# MainBoard_V1p0_PSU.net
KiCad netlist of a schematic drawn in Altium Designer
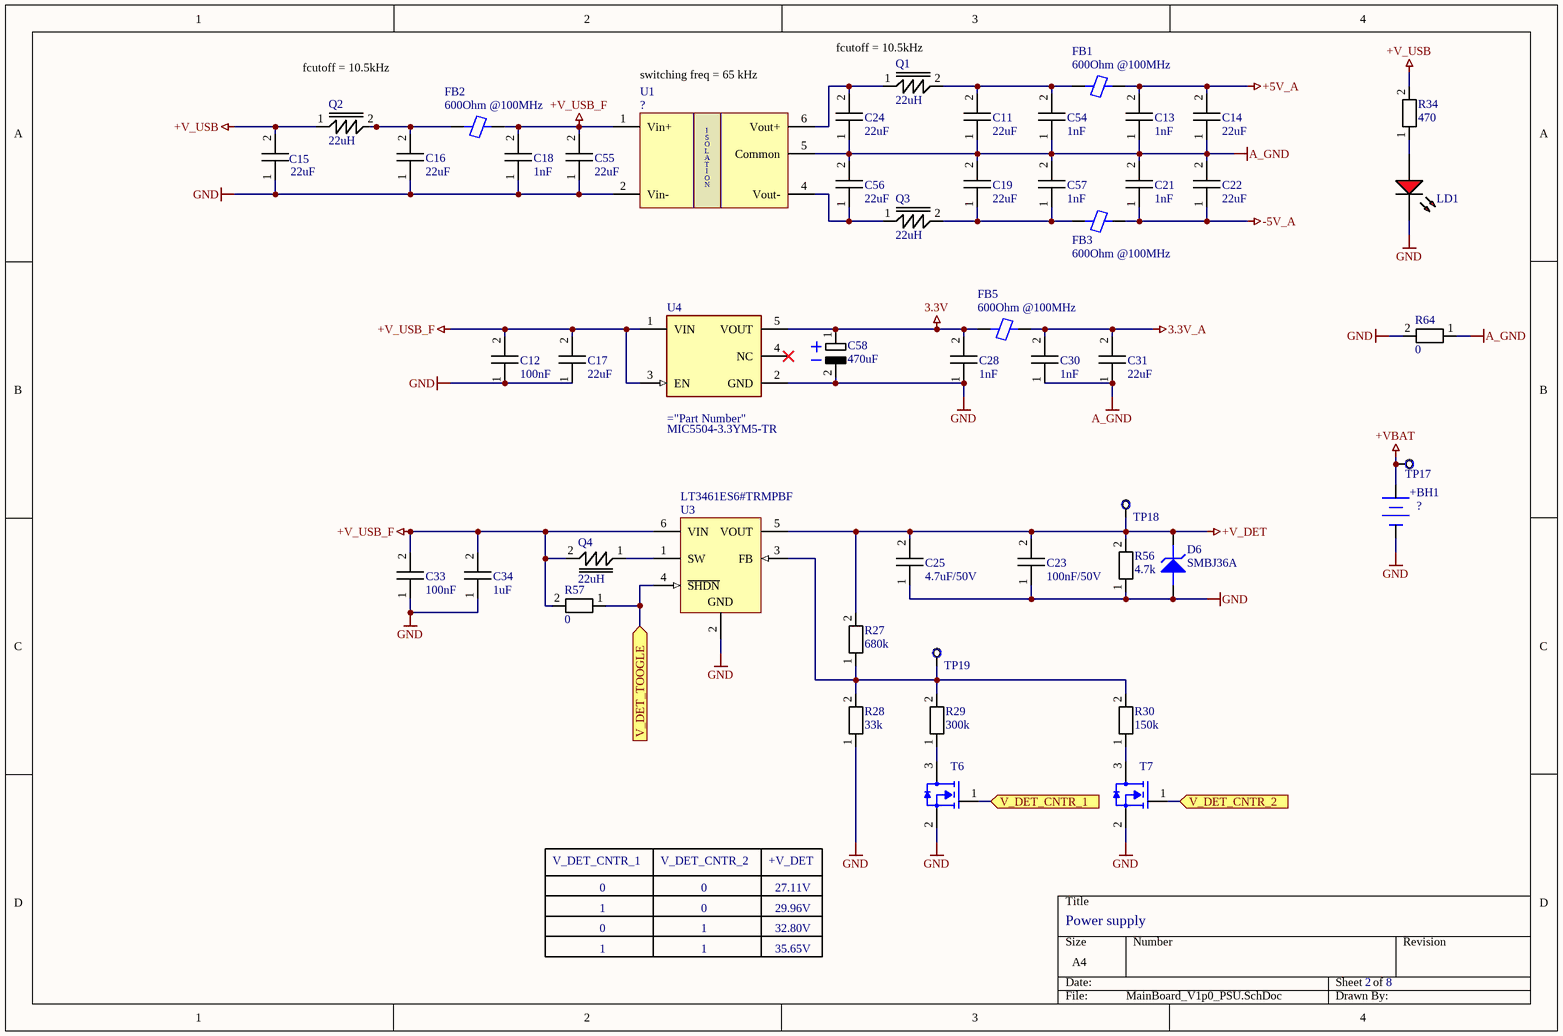
[diagram p0: MainBoard_V1p0_PSU.SchDoc]

(export (version "E")
  (design (tool "Eeschema 10.0.6"))
  (components
    (comp (ref "BH1")
      (value "?")
      (footprint "BATTERY_HOLDER_KEYSTONE_3002")
      (description "KEYSTONE 3002 (CR2032)")
      (libsource (lib "Schlib1") (part "BATTERY_HOLDER"))
    )
    (comp (ref "C11") (value "22uF") (footprint "1210_C") (libsource (lib "Schlib1") (part "CAPACITOR")))
    (comp (ref "C12") (value "100nF") (footprint "0805_C") (libsource (lib "Schlib1") (part "CAPACITOR")))
    (comp (ref "C13") (value "1nF") (footprint "0805_C") (libsource (lib "Schlib1") (part "CAPACITOR")))
    (comp (ref "C14") (value "22uF") (footprint "1210_C") (libsource (lib "Schlib1") (part "CAPACITOR")))
    (comp (ref "C15") (value "22uF") (footprint "1210_C") (libsource (lib "Schlib1") (part "CAPACITOR")))
    (comp (ref "C16") (value "22uF") (footprint "0805_C") (libsource (lib "Schlib1") (part "CAPACITOR")))
    (comp (ref "C17") (value "22uF") (footprint "1210_C") (libsource (lib "Schlib1") (part "CAPACITOR")))
    (comp (ref "C18") (value "1nF") (footprint "0805_C") (libsource (lib "Schlib1") (part "CAPACITOR")))
    (comp (ref "C19") (value "22uF") (footprint "1210_C") (libsource (lib "Schlib1") (part "CAPACITOR")))
    (comp (ref "C21") (value "1nF") (footprint "0805_C") (libsource (lib "Schlib1") (part "CAPACITOR")))
    (comp (ref "C22") (value "22uF") (footprint "1210_C") (libsource (lib "Schlib1") (part "CAPACITOR")))
    (comp (ref "C23") (value "100nF/50V") (footprint "0805_C") (libsource (lib "Schlib1") (part "CAPACITOR")))
    (comp (ref "C24") (value "22uF") (footprint "1210_C") (libsource (lib "Schlib1") (part "CAPACITOR")))
    (comp (ref "C25") (value "4.7uF/50V") (footprint "0805_C") (libsource (lib "Schlib1") (part "CAPACITOR")))
    (comp (ref "C28") (value "1nF") (footprint "0805_C") (libsource (lib "Schlib1") (part "CAPACITOR")))
    (comp (ref "C30") (value "1nF") (footprint "0805_C") (libsource (lib "Schlib1") (part "CAPACITOR")))
    (comp (ref "C31") (value "22uF") (footprint "1210_C") (libsource (lib "Schlib1") (part "CAPACITOR")))
    (comp (ref "C33") (value "100nF") (footprint "0805_C") (libsource (lib "Schlib1") (part "CAPACITOR")))
    (comp (ref "C34") (value "1uF") (footprint "0805_C") (libsource (lib "Schlib1") (part "CAPACITOR")))
    (comp (ref "C54") (value "1nF") (footprint "0805_C") (libsource (lib "Schlib1") (part "CAPACITOR")))
    (comp (ref "C55") (value "22uF") (footprint "1210_C") (libsource (lib "Schlib1") (part "CAPACITOR")))
    (comp (ref "C56") (value "22uF") (footprint "1210_C") (libsource (lib "Schlib1") (part "CAPACITOR")))
    (comp (ref "C57") (value "1nF") (footprint "0805_C") (libsource (lib "Schlib1") (part "CAPACITOR")))
    (comp (ref "C58")
      (value "470uF")
      (footprint "CAPAE9383X110M")
      (libsource (lib "Schlib1") (part "CAPACITOR_ELCO"))
    )
    (comp (ref "D6")
      (value "SMBJ36A")
      (footprint "DO-214AA (SMB)")
      (libsource (lib "Schlib1") (part "DIODE_TVS"))
    )
    (comp (ref "FB1")
      (value "600Ohm @100MHz")
      (footprint "0805_FB")
      (libsource (lib "Schlib1") (part "FERRITE_BEAD"))
    )
    (comp (ref "FB2")
      (value "600Ohm @100MHz")
      (footprint "0805_FB")
      (libsource (lib "Schlib1") (part "FERRITE_BEAD"))
    )
    (comp (ref "FB3")
      (value "600Ohm @100MHz")
      (footprint "0805_FB")
      (libsource (lib "Schlib1") (part "FERRITE_BEAD"))
    )
    (comp (ref "FB5")
      (value "600Ohm @100MHz")
      (footprint "0805_FB")
      (libsource (lib "Schlib1") (part "FERRITE_BEAD"))
    )
    (comp (ref "LD1")
      (value "LED_RED")
      (footprint "LED_SMD_90DEG_RED")
      (libsource (lib "Schlib1") (part "LED_RED"))
    )
    (comp (ref "Q1") (value "22uH") (footprint "1210") (libsource (lib "Schlib1") (part "COIL")))
    (comp (ref "Q2") (value "22uH") (footprint "1210") (libsource (lib "Schlib1") (part "COIL")))
    (comp (ref "Q3") (value "22uH") (footprint "1210") (libsource (lib "Schlib1") (part "COIL")))
    (comp (ref "Q4") (value "22uH") (footprint "1210") (libsource (lib "Schlib1") (part "COIL")))
    (comp (ref "R27") (value "680k") (footprint "0805") (libsource (lib "Schlib1") (part "RESISTOR")))
    (comp (ref "R28") (value "33k") (footprint "0805") (libsource (lib "Schlib1") (part "RESISTOR")))
    (comp (ref "R29") (value "300k") (footprint "0805") (libsource (lib "Schlib1") (part "RESISTOR")))
    (comp (ref "R30") (value "150k") (footprint "0805") (libsource (lib "Schlib1") (part "RESISTOR")))
    (comp (ref "R34") (value "470") (footprint "0805") (libsource (lib "Schlib1") (part "RESISTOR")))
    (comp (ref "R56") (value "4.7k") (footprint "0805") (libsource (lib "Schlib1") (part "RESISTOR")))
    (comp (ref "R57") (value "0") (footprint "0805") (libsource (lib "Schlib1") (part "RESISTOR")))
    (comp (ref "R64") (value "0") (footprint "0805") (libsource (lib "Schlib1") (part "RESISTOR")))
    (comp (ref "T6")
      (value "MMBF170")
      (footprint "SOT23")
      (description "N MOSFET")
      (libsource (lib "Schlib1") (part "MMBF170"))
    )
    (comp (ref "T7")
      (value "MMBF170")
      (footprint "SOT23")
      (description "N MOSFET")
      (libsource (lib "Schlib1") (part "MMBF170"))
    )
    (comp (ref "TP17") (value "?") (footprint "PAD_40") (libsource (lib "Schlib1") (part "TESTPOINT")))
    (comp (ref "TP18") (value "?") (footprint "PAD_40") (libsource (lib "Schlib1") (part "TESTPOINT")))
    (comp (ref "TP19") (value "?") (footprint "PAD_40") (libsource (lib "Schlib1") (part "TESTPOINT")))
    (comp (ref "U1")
      (value "?")
      (footprint "SIP_6")
      (description "MEA1D0505SC Isolated DC/DC Converters +/-5V 100mA")
      (libsource (lib "pwr_mgt") (part "NKA0505SC"))
    )
    (comp (ref "U3")
      (value "LT3461ES6#TRMPBF")
      (footprint "LT-S6-6-TSOT-23_L")
      (libsource (lib "pwr_mgt") (part "LT3461"))
    )
    (comp (ref "U4")
      (value "MIC5504-3.3YM5-TR")
      (footprint "SOT23-5")
      (libsource (lib "pwr_mgt") (part "MIC5504-3.3YM5-TR"))
    )
  )
  (nets
    (net (code "1") (name "+5V_A") (class "Default")
      (node (ref "C13") (pin "2") (pinfunction "2_2") (pintype "passive"))
      (node (ref "C14") (pin "2") (pinfunction "2_2") (pintype "passive"))
      (node (ref "FB1") (pin "2") (pinfunction "2_2") (pintype "passive"))
    )
    (net (code "2") (name "+VBAT") (class "Default")
      (node (ref "BH1") (pin "1") (pinfunction "1_1") (pintype "passive"))
      (node (ref "TP17") (pin "1") (pinfunction "1_1") (pintype "passive"))
    )
    (net (code "3") (name "+V_DET") (class "Default")
      (node (ref "C23") (pin "2") (pinfunction "2_2") (pintype "passive"))
      (node (ref "C25") (pin "2") (pinfunction "2_2") (pintype "passive"))
      (node (ref "D6") (pin "K") (pinfunction "K_K") (pintype "passive"))
      (node (ref "R27") (pin "2") (pinfunction "1_2") (pintype "passive"))
      (node (ref "R56") (pin "2") (pinfunction "1_2") (pintype "passive"))
      (node (ref "TP18") (pin "1") (pinfunction "1_1") (pintype "passive"))
      (node (ref "U3") (pin "5") (pinfunction "VOUT_5") (pintype "power_in"))
    )
    (net (code "4") (name "+V_USB") (class "Default")
      (node (ref "C15") (pin "2") (pinfunction "2_2") (pintype "passive"))
      (node (ref "Q2") (pin "1") (pinfunction "1_1") (pintype "passive"))
      (node (ref "R34") (pin "2") (pinfunction "1_2") (pintype "passive"))
    )
    (net (code "5") (name "+V_USB_F") (class "Default")
      (node (ref "C12") (pin "2") (pinfunction "2_2") (pintype "passive"))
      (node (ref "C17") (pin "2") (pinfunction "2_2") (pintype "passive"))
      (node (ref "C18") (pin "2") (pinfunction "2_2") (pintype "passive"))
      (node (ref "C33") (pin "2") (pinfunction "2_2") (pintype "passive"))
      (node (ref "C34") (pin "2") (pinfunction "2_2") (pintype "passive"))
      (node (ref "C55") (pin "2") (pinfunction "2_2") (pintype "passive"))
      (node (ref "FB2") (pin "2") (pinfunction "2_2") (pintype "passive"))
      (node (ref "Q4") (pin "2") (pinfunction "2_2") (pintype "passive"))
      (node (ref "R57") (pin "2") (pinfunction "1_2") (pintype "passive"))
      (node (ref "U1") (pin "1") (pinfunction "Vin+_1") (pintype "passive"))
      (node (ref "U3") (pin "6") (pinfunction "VIN_6") (pintype "power_in"))
      (node (ref "U4") (pin "1") (pinfunction "VIN_1") (pintype "power_in"))
      (node (ref "U4") (pin "3") (pinfunction "EN_3") (pintype "input"))
    )
    (net (code "6") (name "-5V_A") (class "Default")
      (node (ref "C21") (pin "1") (pinfunction "1_1") (pintype "passive"))
      (node (ref "C22") (pin "1") (pinfunction "1_1") (pintype "passive"))
      (node (ref "FB3") (pin "2") (pinfunction "2_2") (pintype "passive"))
    )
    (net (code "7") (name "/V_DET_CNTR_1") (class "Default")
      (node (ref "T6") (pin "1") (pinfunction "Gate_1") (pintype "passive"))
    )
    (net (code "8") (name "/V_DET_CNTR_2") (class "Default")
      (node (ref "T7") (pin "1") (pinfunction "Gate_1") (pintype "passive"))
    )
    (net (code "9") (name "/V_DET_TOOGLE") (class "Default")
      (node (ref "R57") (pin "1") (pinfunction "0_1") (pintype "passive"))
      (node (ref "U3") (pin "4") (pinfunction "~{SHDN}_4") (pintype "input"))
    )
    (net (code "10") (name "3.3V") (class "Default")
      (node (ref "C28") (pin "2") (pinfunction "2_2") (pintype "passive"))
      (node (ref "C58") (pin "1") (pinfunction "1_1") (pintype "passive"))
      (node (ref "FB5") (pin "1") (pinfunction "1_1") (pintype "passive"))
      (node (ref "U4") (pin "5") (pinfunction "VOUT_5") (pintype "power_in"))
    )
    (net (code "11") (name "3.3V_A") (class "Default")
      (node (ref "C30") (pin "2") (pinfunction "2_2") (pintype "passive"))
      (node (ref "C31") (pin "2") (pinfunction "2_2") (pintype "passive"))
      (node (ref "FB5") (pin "2") (pinfunction "2_2") (pintype "passive"))
    )
    (net (code "12") (name "A_GND") (class "Default")
      (node (ref "C11") (pin "1") (pinfunction "1_1") (pintype "passive"))
      (node (ref "C13") (pin "1") (pinfunction "1_1") (pintype "passive"))
      (node (ref "C14") (pin "1") (pinfunction "1_1") (pintype "passive"))
      (node (ref "C19") (pin "2") (pinfunction "2_2") (pintype "passive"))
      (node (ref "C21") (pin "2") (pinfunction "2_2") (pintype "passive"))
      (node (ref "C22") (pin "2") (pinfunction "2_2") (pintype "passive"))
      (node (ref "C24") (pin "1") (pinfunction "1_1") (pintype "passive"))
      (node (ref "C30") (pin "1") (pinfunction "1_1") (pintype "passive"))
      (node (ref "C31") (pin "1") (pinfunction "1_1") (pintype "passive"))
      (node (ref "C54") (pin "1") (pinfunction "1_1") (pintype "passive"))
      (node (ref "C56") (pin "2") (pinfunction "2_2") (pintype "passive"))
      (node (ref "C57") (pin "2") (pinfunction "2_2") (pintype "passive"))
      (node (ref "R64") (pin "1") (pinfunction "0_1") (pintype "passive"))
      (node (ref "U1") (pin "5") (pinfunction "Common_5") (pintype "passive"))
    )
    (net (code "13") (name "GND") (class "Default")
      (node (ref "BH1") (pin "2") (pinfunction "2_2") (pintype "passive"))
      (node (ref "C12") (pin "1") (pinfunction "1_1") (pintype "passive"))
      (node (ref "C15") (pin "1") (pinfunction "1_1") (pintype "passive"))
      (node (ref "C16") (pin "1") (pinfunction "1_1") (pintype "passive"))
      (node (ref "C17") (pin "1") (pinfunction "1_1") (pintype "passive"))
      (node (ref "C18") (pin "1") (pinfunction "1_1") (pintype "passive"))
      (node (ref "C23") (pin "1") (pinfunction "1_1") (pintype "passive"))
      (node (ref "C25") (pin "1") (pinfunction "1_1") (pintype "passive"))
      (node (ref "C28") (pin "1") (pinfunction "1_1") (pintype "passive"))
      (node (ref "C33") (pin "1") (pinfunction "1_1") (pintype "passive"))
      (node (ref "C34") (pin "1") (pinfunction "1_1") (pintype "passive"))
      (node (ref "C55") (pin "1") (pinfunction "1_1") (pintype "passive"))
      (node (ref "C58") (pin "2") (pinfunction "2_2") (pintype "passive"))
      (node (ref "D6") (pin "A") (pinfunction "A_A") (pintype "passive"))
      (node (ref "LD1") (pin "K") (pinfunction "K_K") (pintype "passive"))
      (node (ref "R28") (pin "1") (pinfunction "0_1") (pintype "passive"))
      (node (ref "R56") (pin "1") (pinfunction "0_1") (pintype "passive"))
      (node (ref "R64") (pin "2") (pinfunction "1_2") (pintype "passive"))
      (node (ref "T6") (pin "2") (pinfunction "Source_2") (pintype "passive"))
      (node (ref "T7") (pin "2") (pinfunction "Source_2") (pintype "passive"))
      (node (ref "U1") (pin "2") (pinfunction "Vin-_2") (pintype "passive"))
      (node (ref "U3") (pin "2") (pinfunction "GND_2") (pintype "power_in"))
      (node (ref "U4") (pin "2") (pinfunction "GND_2") (pintype "power_in"))
    )
    (net (code "14") (name "Net-(C11-Pad2)") (class "Default")
      (node (ref "C11") (pin "2") (pinfunction "2_2") (pintype "passive"))
      (node (ref "C54") (pin "2") (pinfunction "2_2") (pintype "passive"))
      (node (ref "FB1") (pin "1") (pinfunction "1_1") (pintype "passive"))
      (node (ref "Q1") (pin "2") (pinfunction "2_2") (pintype "passive"))
    )
    (net (code "15") (name "Net-(C16-Pad2)") (class "Default")
      (node (ref "C16") (pin "2") (pinfunction "2_2") (pintype "passive"))
      (node (ref "FB2") (pin "1") (pinfunction "1_1") (pintype "passive"))
      (node (ref "Q2") (pin "2") (pinfunction "2_2") (pintype "passive"))
    )
    (net (code "16") (name "Net-(C19-Pad1)") (class "Default")
      (node (ref "C19") (pin "1") (pinfunction "1_1") (pintype "passive"))
      (node (ref "C57") (pin "1") (pinfunction "1_1") (pintype "passive"))
      (node (ref "FB3") (pin "1") (pinfunction "1_1") (pintype "passive"))
      (node (ref "Q3") (pin "2") (pinfunction "2_2") (pintype "passive"))
    )
    (net (code "17") (name "Net-(R27-0)") (class "Default")
      (node (ref "R27") (pin "1") (pinfunction "0_1") (pintype "passive"))
      (node (ref "R28") (pin "2") (pinfunction "1_2") (pintype "passive"))
      (node (ref "R29") (pin "2") (pinfunction "1_2") (pintype "passive"))
      (node (ref "R30") (pin "2") (pinfunction "1_2") (pintype "passive"))
      (node (ref "TP19") (pin "1") (pinfunction "1_1") (pintype "passive"))
      (node (ref "U3") (pin "3") (pinfunction "FB_3") (pintype "input"))
    )
    (net (code "18") (name "Net-(R29-0)") (class "Default")
      (node (ref "R29") (pin "1") (pinfunction "0_1") (pintype "passive"))
      (node (ref "T6") (pin "3") (pinfunction "Drain_3") (pintype "passive"))
    )
    (net (code "19") (name "Net-(R30-0)") (class "Default")
      (node (ref "R30") (pin "1") (pinfunction "0_1") (pintype "passive"))
      (node (ref "T7") (pin "3") (pinfunction "Drain_3") (pintype "passive"))
    )
    (net (code "20") (name "Net-(R34-0)") (class "Default")
      (node (ref "LD1") (pin "A") (pinfunction "A_A") (pintype "passive"))
      (node (ref "R34") (pin "1") (pinfunction "0_1") (pintype "passive"))
    )
    (net (code "21") (name "Net-(U1-Vout+)") (class "Default")
      (node (ref "C24") (pin "2") (pinfunction "2_2") (pintype "passive"))
      (node (ref "Q1") (pin "1") (pinfunction "1_1") (pintype "passive"))
      (node (ref "U1") (pin "6") (pinfunction "Vout+_6") (pintype "passive"))
    )
    (net (code "22") (name "Net-(U1-Vout-)") (class "Default")
      (node (ref "C56") (pin "1") (pinfunction "1_1") (pintype "passive"))
      (node (ref "Q3") (pin "1") (pinfunction "1_1") (pintype "passive"))
      (node (ref "U1") (pin "4") (pinfunction "Vout-_4") (pintype "passive"))
    )
    (net (code "23") (name "Net-(U3-SW)") (class "Default")
      (node (ref "Q4") (pin "1") (pinfunction "1_1") (pintype "passive"))
      (node (ref "U3") (pin "1") (pinfunction "SW_1") (pintype "passive"))
    )
    (net (code "24") (name "unconnected-(U4-NC-Pad4)") (class "Default")
      (node (ref "U4") (pin "4") (pinfunction "NC_4") (pintype "passive+no_connect"))
    )
  )
)
